# Center_Console_-_LED_Interface.net
KiCad netlist of a schematic drawn in Altium Designer
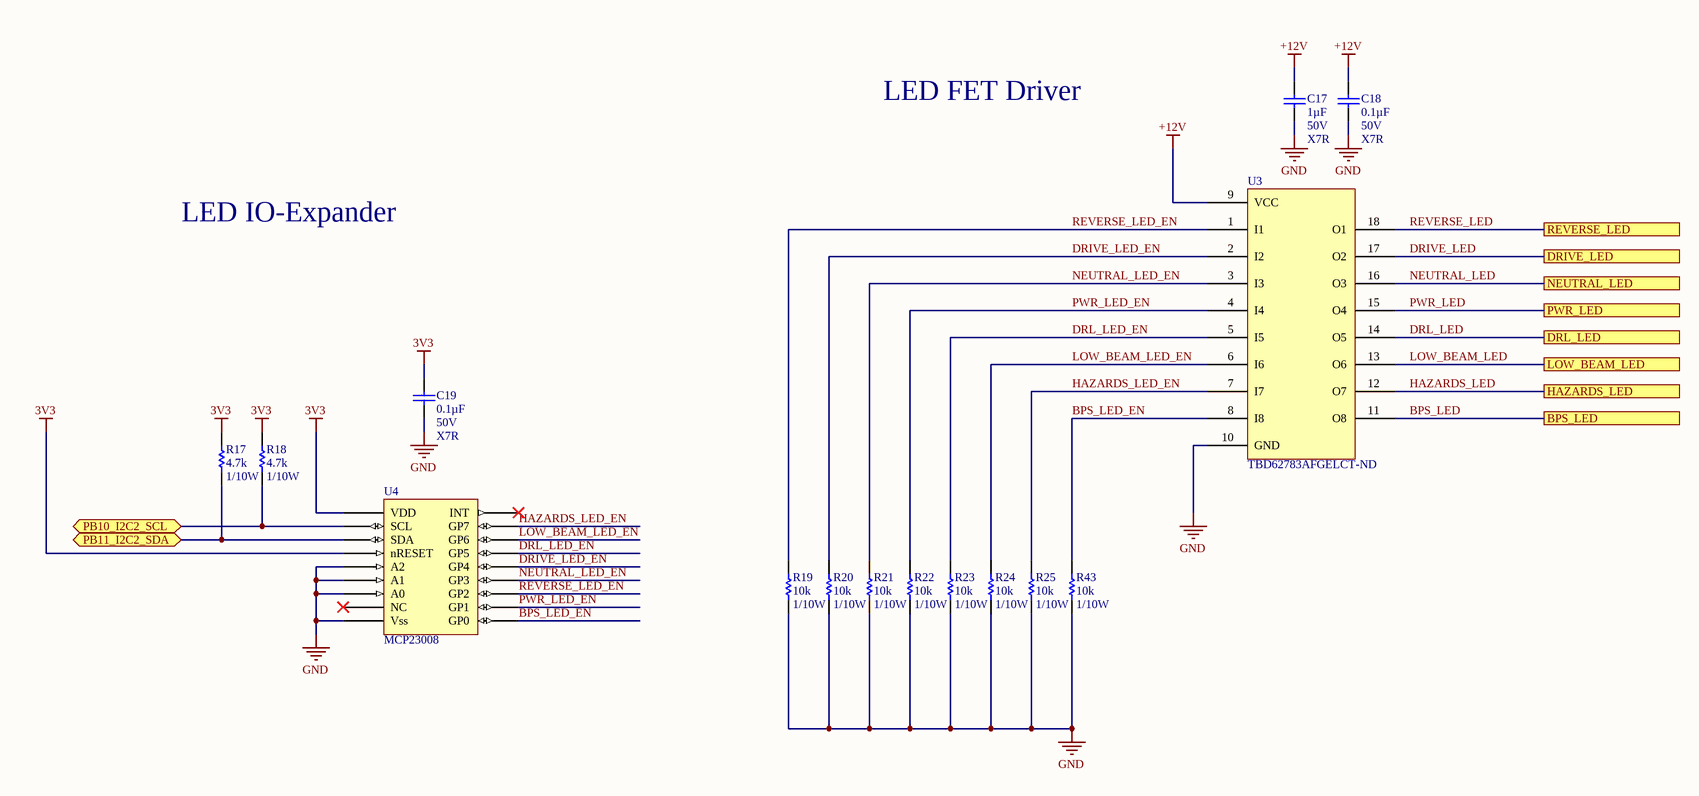
[diagram p0: Center Console - LED Interface.SchDoc]

(export (version "E")
  (design (tool "Eeschema 10.0.6"))
  (components
    (comp (ref "C17")
      (value "CAP CER 1UF 50V 10% X7R 0603")
      (footprint "CAP, 0603")
      (description "1µF ±10% 50V Ceramic Capacitor X7R 0603 (1608 Metric)")
      (fields
        (field (name "TOLERANCE") "±10%")
        (field (name "CAPACITANCE") "1µF")
        (field (name "VOLTAGE") "50V")
        (field (name "TEMPERATURE COEFFICIENT") "X7R")
      )
      (libsource (lib "Schematic Diagrams") (part "CAP CER 1UF 50V 10% X7R 0603"))
    )
    (comp (ref "C18")
      (value "CAP CER 0.1UF 50V 10% X7R 0603")
      (footprint "CAP, 0603")
      (description "0.10µF ±10% 50V Ceramic Capacitor X7R 0603 (1608 Metric)")
      (fields
        (field (name "TOLERANCE") "±10%")
        (field (name "CAPACITANCE") "0.1µF")
        (field (name "VOLTAGE") "50V")
        (field (name "TEMPERATURE COEFFICIENT") "X7R")
      )
      (libsource (lib "Schematic Diagrams") (part "CAP CER 0.1UF 50V 10% X7R 0603"))
    )
    (comp (ref "C19")
      (value "CAP CER 0.1UF 50V 10% X7R 0603")
      (footprint "CAP, 0603")
      (description "0.10µF ±10% 50V Ceramic Capacitor X7R 0603 (1608 Metric)")
      (fields
        (field (name "TOLERANCE") "±10%")
        (field (name "CAPACITANCE") "0.1µF")
        (field (name "VOLTAGE") "50V")
        (field (name "TEMPERATURE COEFFICIENT") "X7R")
      )
      (libsource (lib "Schematic Diagrams") (part "CAP CER 0.1UF 50V 10% X7R 0603"))
    )
    (comp (ref "R17")
      (value "RES 4.7K OHM 1% 1/10W 0603")
      (footprint "RES, 0603")
      (description "4.7k Ohm ±1% 0.1W, 1/10W Chip Resistor 0603 (1608 Metric) Moisture Resistant Thick Film")
      (fields
        (field (name "TOLERANCE") "±1%")
        (field (name "RESISTANCE (OHMS)") "4.7k")
        (field (name "POWER (WATTS)") "1/10W")
      )
      (libsource (lib "Schematic Diagrams") (part "RES 4.7K OHM 1% 1/10W 0603"))
    )
    (comp (ref "R18")
      (value "RES 4.7K OHM 1% 1/10W 0603")
      (footprint "RES, 0603")
      (description "4.7k Ohm ±1% 0.1W, 1/10W Chip Resistor 0603 (1608 Metric) Moisture Resistant Thick Film")
      (fields
        (field (name "TOLERANCE") "±1%")
        (field (name "RESISTANCE (OHMS)") "4.7k")
        (field (name "POWER (WATTS)") "1/10W")
      )
      (libsource (lib "Schematic Diagrams") (part "RES 4.7K OHM 1% 1/10W 0603"))
    )
    (comp (ref "R19")
      (value "RES 10K OHM 1% 1/10W 0603")
      (footprint "RES, 0603")
      (description "RES SMD 10K OHM 1% 1/10W 0603")
      (fields
        (field (name "TOLERANCE") "±1%")
        (field (name "RESISTANCE") "10k")
        (field (name "POWER") "1/10W")
      )
      (libsource (lib "Schematic Diagrams") (part "RES 10K OHM 1% 1/10W 0603"))
    )
    (comp (ref "R20")
      (value "RES 10K OHM 1% 1/10W 0603")
      (footprint "RES, 0603")
      (description "RES SMD 10K OHM 1% 1/10W 0603")
      (fields
        (field (name "TOLERANCE") "±1%")
        (field (name "RESISTANCE") "10k")
        (field (name "POWER") "1/10W")
      )
      (libsource (lib "Schematic Diagrams") (part "RES 10K OHM 1% 1/10W 0603"))
    )
    (comp (ref "R21")
      (value "RES 10K OHM 1% 1/10W 0603")
      (footprint "RES, 0603")
      (description "RES SMD 10K OHM 1% 1/10W 0603")
      (fields
        (field (name "TOLERANCE") "±1%")
        (field (name "RESISTANCE") "10k")
        (field (name "POWER") "1/10W")
      )
      (libsource (lib "Schematic Diagrams") (part "RES 10K OHM 1% 1/10W 0603"))
    )
    (comp (ref "R22")
      (value "RES 10K OHM 1% 1/10W 0603")
      (footprint "RES, 0603")
      (description "RES SMD 10K OHM 1% 1/10W 0603")
      (fields
        (field (name "TOLERANCE") "±1%")
        (field (name "RESISTANCE") "10k")
        (field (name "POWER") "1/10W")
      )
      (libsource (lib "Schematic Diagrams") (part "RES 10K OHM 1% 1/10W 0603"))
    )
    (comp (ref "R23")
      (value "RES 10K OHM 1% 1/10W 0603")
      (footprint "RES, 0603")
      (description "RES SMD 10K OHM 1% 1/10W 0603")
      (fields
        (field (name "TOLERANCE") "±1%")
        (field (name "RESISTANCE") "10k")
        (field (name "POWER") "1/10W")
      )
      (libsource (lib "Schematic Diagrams") (part "RES 10K OHM 1% 1/10W 0603"))
    )
    (comp (ref "R24")
      (value "RES 10K OHM 1% 1/10W 0603")
      (footprint "RES, 0603")
      (description "RES SMD 10K OHM 1% 1/10W 0603")
      (fields
        (field (name "TOLERANCE") "±1%")
        (field (name "RESISTANCE") "10k")
        (field (name "POWER") "1/10W")
      )
      (libsource (lib "Schematic Diagrams") (part "RES 10K OHM 1% 1/10W 0603"))
    )
    (comp (ref "R25")
      (value "RES 10K OHM 1% 1/10W 0603")
      (footprint "RES, 0603")
      (description "RES SMD 10K OHM 1% 1/10W 0603")
      (fields
        (field (name "TOLERANCE") "±1%")
        (field (name "RESISTANCE") "10k")
        (field (name "POWER") "1/10W")
      )
      (libsource (lib "Schematic Diagrams") (part "RES 10K OHM 1% 1/10W 0603"))
    )
    (comp (ref "R43")
      (value "RES 10K OHM 1% 1/10W 0603")
      (footprint "RES, 0603")
      (description "RES SMD 10K OHM 1% 1/10W 0603")
      (fields
        (field (name "TOLERANCE") "±1%")
        (field (name "RESISTANCE") "10k")
        (field (name "POWER") "1/10W")
      )
      (libsource (lib "Schematic Diagrams") (part "RES 10K OHM 1% 1/10W 0603"))
    )
    (comp (ref "U3")
      (value "IC LOAD SWITCH 8CH 0.5A 18SOP")
      (footprint "IC LOAD SWITCH 8CH 0.5A 18-SSOP")
      (description "IC LOAD SWITCH 8CHANNEL 0.5A 18SOP")
      (fields
        (field (name "MANUFACTURER") "Toshiba")
        (field (name "MANUFACTURER PART NUMBER") "TBD62783AFG,EL")
        (field (name "SUPPLIER PART NUMBER 1") "TBD62783AFGELCT-ND")
      )
      (libsource (lib "Schematic Diagrams") (part "IC LOAD SWITCH 8CH 0.5A 18SOP"))
    )
    (comp (ref "U4")
      (value "MCP23008")
      (footprint "IC 18SOIC")
      (description "MCP23008 I/O Expander 8B+1Int 18P SOIC")
      (fields
        (field (name "MANUFACTURER") "Microchip Technology")
        (field (name "MANUFACTURER PART NUMBER") "MCP23008T-E/SO")
      )
      (libsource (lib "Schematic Diagrams") (part "IC I/O EXPANDER I2C 8B 18SOIC"))
    )
  )
  (nets
    (net (code "1") (name "+12V") (class "Default")
      (node (ref "C17") (pin "1") (pinfunction "1_1") (pintype "passive"))
      (node (ref "C18") (pin "1") (pinfunction "1_1") (pintype "passive"))
      (node (ref "U3") (pin "9") (pinfunction "VCC_9") (pintype "passive"))
    )
    (net (code "2") (name "/BPS_LED") (class "Default")
      (node (ref "U3") (pin "11") (pinfunction "O8_11") (pintype "passive"))
    )
    (net (code "3") (name "/BPS_LED_EN") (class "Default")
      (node (ref "R43") (pin "1") (pinfunction "1_1") (pintype "passive"))
      (node (ref "U3") (pin "8") (pinfunction "I8_8") (pintype "passive"))
      (node (ref "U4") (pin "10") (pinfunction "GP0_10") (pintype "bidirectional"))
    )
    (net (code "4") (name "/DRIVE_LED") (class "Default")
      (node (ref "U3") (pin "17") (pinfunction "O2_17") (pintype "passive"))
    )
    (net (code "5") (name "/DRIVE_LED_EN") (class "Default")
      (node (ref "R20") (pin "1") (pinfunction "1_1") (pintype "passive"))
      (node (ref "U3") (pin "2") (pinfunction "I2_2") (pintype "passive"))
      (node (ref "U4") (pin "14") (pinfunction "GP4_14") (pintype "bidirectional"))
    )
    (net (code "6") (name "/DRL_LED") (class "Default")
      (node (ref "U3") (pin "14") (pinfunction "O5_14") (pintype "passive"))
    )
    (net (code "7") (name "/DRL_LED_EN") (class "Default")
      (node (ref "R23") (pin "1") (pinfunction "1_1") (pintype "passive"))
      (node (ref "U3") (pin "5") (pinfunction "I5_5") (pintype "passive"))
      (node (ref "U4") (pin "15") (pinfunction "GP5_15") (pintype "bidirectional"))
    )
    (net (code "8") (name "/HAZARDS_LED") (class "Default")
      (node (ref "U3") (pin "12") (pinfunction "O7_12") (pintype "passive"))
    )
    (net (code "9") (name "/HAZARDS_LED_EN") (class "Default")
      (node (ref "R25") (pin "1") (pinfunction "1_1") (pintype "passive"))
      (node (ref "U3") (pin "7") (pinfunction "I7_7") (pintype "passive"))
      (node (ref "U4") (pin "17") (pinfunction "GP7_17") (pintype "bidirectional"))
    )
    (net (code "10") (name "/LOW_BEAM_LED") (class "Default")
      (node (ref "U3") (pin "13") (pinfunction "O6_13") (pintype "passive"))
    )
    (net (code "11") (name "/LOW_BEAM_LED_EN") (class "Default")
      (node (ref "R24") (pin "1") (pinfunction "1_1") (pintype "passive"))
      (node (ref "U3") (pin "6") (pinfunction "I6_6") (pintype "passive"))
      (node (ref "U4") (pin "16") (pinfunction "GP6_16") (pintype "bidirectional"))
    )
    (net (code "12") (name "/NEUTRAL_LED") (class "Default")
      (node (ref "U3") (pin "16") (pinfunction "O3_16") (pintype "passive"))
    )
    (net (code "13") (name "/NEUTRAL_LED_EN") (class "Default")
      (node (ref "R21") (pin "1") (pinfunction "1_1") (pintype "passive"))
      (node (ref "U3") (pin "3") (pinfunction "I3_3") (pintype "passive"))
      (node (ref "U4") (pin "13") (pinfunction "GP3_13") (pintype "bidirectional"))
    )
    (net (code "14") (name "/PB10_I2C2_SCL") (class "Default")
      (node (ref "R18") (pin "2") (pinfunction "2_2") (pintype "passive"))
      (node (ref "U4") (pin "1") (pinfunction "SCL_1") (pintype "bidirectional"))
    )
    (net (code "15") (name "/PB11_I2C2_SDA") (class "Default")
      (node (ref "R17") (pin "2") (pinfunction "2_2") (pintype "passive"))
      (node (ref "U4") (pin "2") (pinfunction "SDA_2") (pintype "bidirectional"))
    )
    (net (code "16") (name "/PWR_LED") (class "Default")
      (node (ref "U3") (pin "15") (pinfunction "O4_15") (pintype "passive"))
    )
    (net (code "17") (name "/PWR_LED_EN") (class "Default")
      (node (ref "R22") (pin "1") (pinfunction "1_1") (pintype "passive"))
      (node (ref "U3") (pin "4") (pinfunction "I4_4") (pintype "passive"))
      (node (ref "U4") (pin "11") (pinfunction "GP1_11") (pintype "bidirectional"))
    )
    (net (code "18") (name "/REVERSE_LED") (class "Default")
      (node (ref "U3") (pin "18") (pinfunction "O1_18") (pintype "passive"))
    )
    (net (code "19") (name "/REVERSE_LED_EN") (class "Default")
      (node (ref "R19") (pin "1") (pinfunction "1_1") (pintype "passive"))
      (node (ref "U3") (pin "1") (pinfunction "I1_1") (pintype "passive"))
      (node (ref "U4") (pin "12") (pinfunction "GP2_12") (pintype "bidirectional"))
    )
    (net (code "20") (name "3V3") (class "Default")
      (node (ref "C19") (pin "1") (pinfunction "1_1") (pintype "passive"))
      (node (ref "R17") (pin "1") (pinfunction "1_1") (pintype "passive"))
      (node (ref "R18") (pin "1") (pinfunction "1_1") (pintype "passive"))
      (node (ref "U4") (pin "18") (pinfunction "VDD_18") (pintype "power_in"))
      (node (ref "U4") (pin "6") (pinfunction "nRESET_6") (pintype "input"))
    )
    (net (code "21") (name "GND") (class "Default")
      (node (ref "C17") (pin "2") (pinfunction "2_2") (pintype "passive"))
      (node (ref "C18") (pin "2") (pinfunction "2_2") (pintype "passive"))
      (node (ref "C19") (pin "2") (pinfunction "2_2") (pintype "passive"))
      (node (ref "R19") (pin "2") (pinfunction "2_2") (pintype "passive"))
      (node (ref "R20") (pin "2") (pinfunction "2_2") (pintype "passive"))
      (node (ref "R21") (pin "2") (pinfunction "2_2") (pintype "passive"))
      (node (ref "R22") (pin "2") (pinfunction "2_2") (pintype "passive"))
      (node (ref "R23") (pin "2") (pinfunction "2_2") (pintype "passive"))
      (node (ref "R24") (pin "2") (pinfunction "2_2") (pintype "passive"))
      (node (ref "R25") (pin "2") (pinfunction "2_2") (pintype "passive"))
      (node (ref "R43") (pin "2") (pinfunction "2_2") (pintype "passive"))
      (node (ref "U3") (pin "10") (pinfunction "GND_10") (pintype "passive"))
      (node (ref "U4") (pin "3") (pinfunction "A2_3") (pintype "input"))
      (node (ref "U4") (pin "4") (pinfunction "A1_4") (pintype "input"))
      (node (ref "U4") (pin "5") (pinfunction "A0_5") (pintype "input"))
      (node (ref "U4") (pin "9") (pinfunction "Vss_9") (pintype "power_in"))
    )
    (net (code "22") (name "unconnected-(U4-INT-Pad8)") (class "Default")
      (node (ref "U4") (pin "8") (pinfunction "INT_8") (pintype "output+no_connect"))
    )
    (net (code "23") (name "unconnected-(U4-NC-Pad7)") (class "Default")
      (node (ref "U4") (pin "7") (pinfunction "NC_7") (pintype "passive+no_connect"))
    )
  )
)
